# Sampler.net
KiCad netlist of a schematic drawn in Altium Designer
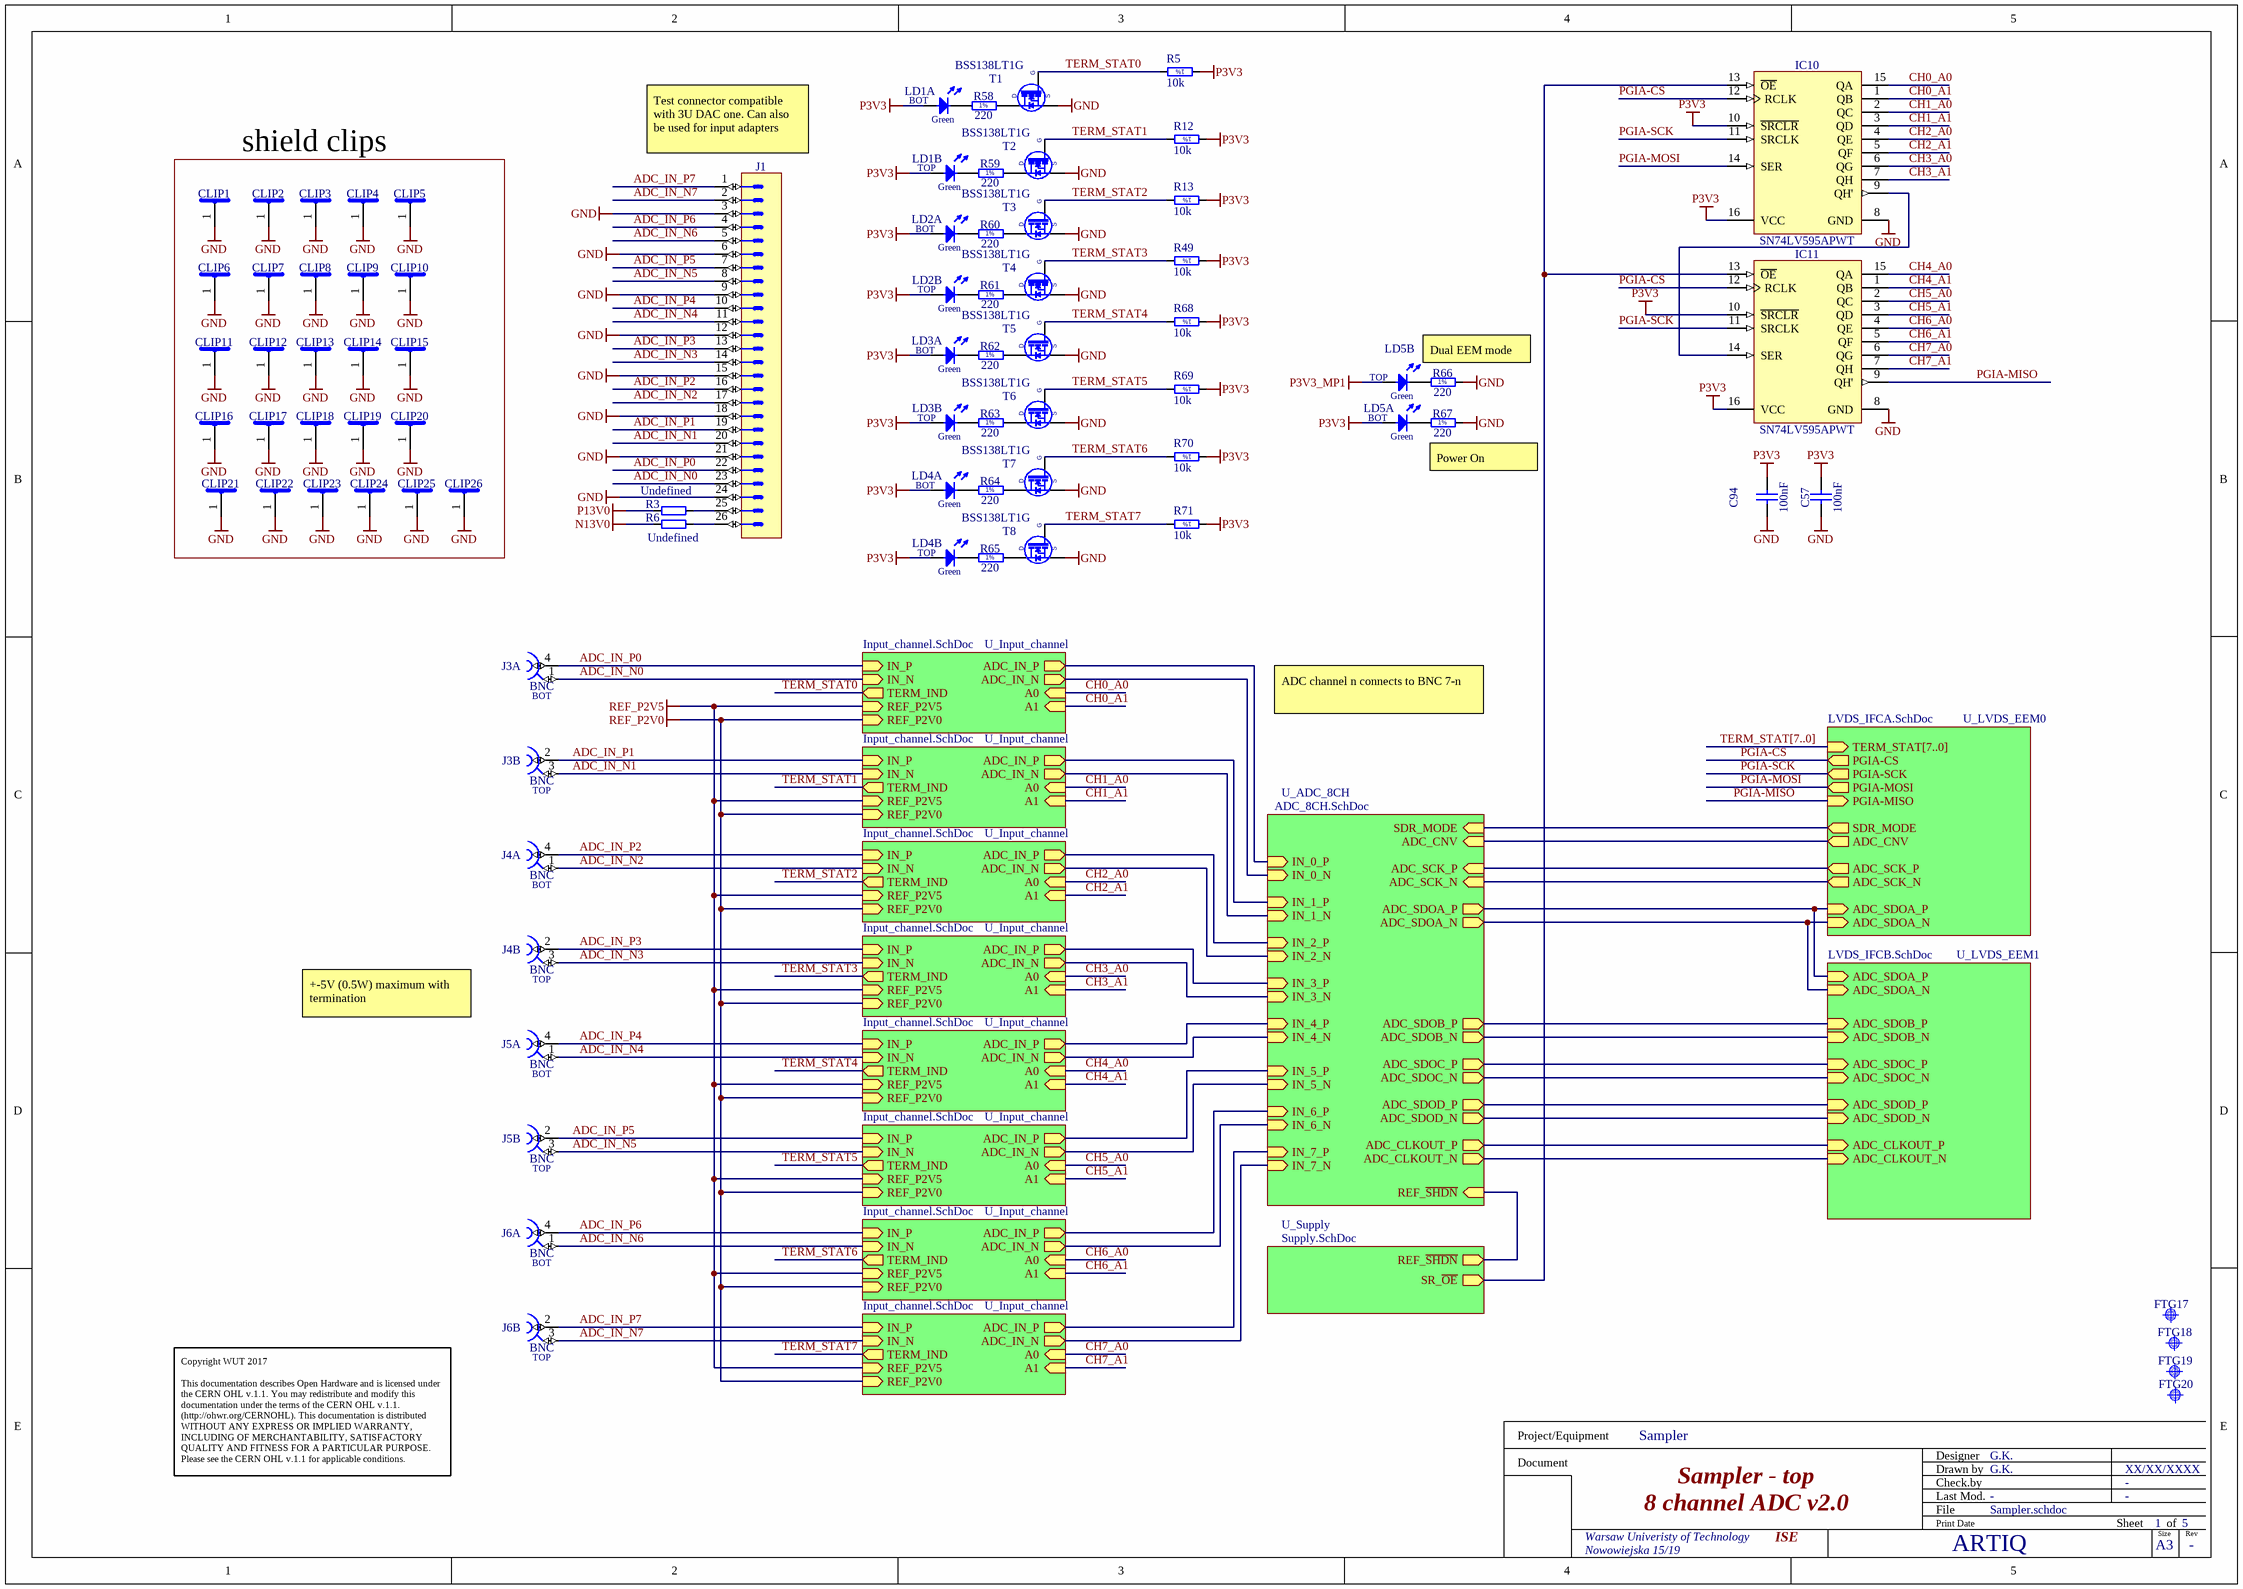
[diagram p0: Sampler.schdoc]

(export (version "E")
  (design (tool "Eeschema 10.0.6"))
  (components
    (comp (ref "C57")
      (value "100nF")
      (footprint "CAPC1608X87N")
      (description "Non-polarised capacitor")
      (fields
        (field (name "PART NUMBER") "CC0603_100NF_50V_10%_X7R")
        (field (name "VOLTAGE") "50V")
        (field (name "AUTHOR") "CERN DEM JLC")
      )
      (libsource (lib "Capacitors") (part "Capacitor - non polarized"))
    )
    (comp (ref "C94")
      (value "100nF")
      (footprint "CAPC1608X87N")
      (description "Non-polarised capacitor")
      (fields
        (field (name "PART NUMBER") "CC0603_100NF_50V_10%_X7R")
        (field (name "VOLTAGE") "50V")
        (field (name "AUTHOR") "CERN DEM JLC")
      )
      (libsource (lib "Capacitors") (part "Capacitor - non polarized"))
    )
    (comp (ref "CLIP1")
      (value "S1411-46R")
      (footprint "CLIP_HOLLAND-SHIELDING_LC")
      (description "Surface Mount Clip for PCB Screening Covers")
      (fields (field (name "MANUFACTURER") "HARWIN") (field (name "AUTHOR") "CERN DEM JLC"))
      (libsource (lib "LIBRARY_SCH") (part "SHIELD_CLIP"))
    )
    (comp (ref "CLIP2")
      (value "S1411-46R")
      (footprint "CLIP_HOLLAND-SHIELDING_LC")
      (description "Surface Mount Clip for PCB Screening Covers")
      (fields (field (name "MANUFACTURER") "HARWIN") (field (name "AUTHOR") "CERN DEM JLC"))
      (libsource (lib "LIBRARY_SCH") (part "SHIELD_CLIP"))
    )
    (comp (ref "CLIP3")
      (value "S1411-46R")
      (footprint "CLIP_HOLLAND-SHIELDING_LC")
      (description "Surface Mount Clip for PCB Screening Covers")
      (fields (field (name "MANUFACTURER") "HARWIN") (field (name "AUTHOR") "CERN DEM JLC"))
      (libsource (lib "LIBRARY_SCH") (part "SHIELD_CLIP"))
    )
    (comp (ref "CLIP4")
      (value "S1411-46R")
      (footprint "CLIP_HOLLAND-SHIELDING_LC")
      (description "Surface Mount Clip for PCB Screening Covers")
      (fields (field (name "MANUFACTURER") "HARWIN") (field (name "AUTHOR") "CERN DEM JLC"))
      (libsource (lib "LIBRARY_SCH") (part "SHIELD_CLIP"))
    )
    (comp (ref "CLIP5")
      (value "S1411-46R")
      (footprint "CLIP_HOLLAND-SHIELDING_LC")
      (description "Surface Mount Clip for PCB Screening Covers")
      (fields (field (name "MANUFACTURER") "HARWIN") (field (name "AUTHOR") "CERN DEM JLC"))
      (libsource (lib "LIBRARY_SCH") (part "SHIELD_CLIP"))
    )
    (comp (ref "CLIP6")
      (value "S1411-46R")
      (footprint "CLIP_HOLLAND-SHIELDING_LC")
      (description "Surface Mount Clip for PCB Screening Covers")
      (fields (field (name "MANUFACTURER") "HARWIN") (field (name "AUTHOR") "CERN DEM JLC"))
      (libsource (lib "LIBRARY_SCH") (part "SHIELD_CLIP"))
    )
    (comp (ref "CLIP7")
      (value "S1411-46R")
      (footprint "CLIP_HOLLAND-SHIELDING_LC")
      (description "Surface Mount Clip for PCB Screening Covers")
      (fields (field (name "MANUFACTURER") "HARWIN") (field (name "AUTHOR") "CERN DEM JLC"))
      (libsource (lib "LIBRARY_SCH") (part "SHIELD_CLIP"))
    )
    (comp (ref "CLIP8")
      (value "S1411-46R")
      (footprint "CLIP_HOLLAND-SHIELDING_LC")
      (description "Surface Mount Clip for PCB Screening Covers")
      (fields (field (name "MANUFACTURER") "HARWIN") (field (name "AUTHOR") "CERN DEM JLC"))
      (libsource (lib "LIBRARY_SCH") (part "SHIELD_CLIP"))
    )
    (comp (ref "CLIP9")
      (value "S1411-46R")
      (footprint "CLIP_HOLLAND-SHIELDING_LC")
      (description "Surface Mount Clip for PCB Screening Covers")
      (fields (field (name "MANUFACTURER") "HARWIN") (field (name "AUTHOR") "CERN DEM JLC"))
      (libsource (lib "LIBRARY_SCH") (part "SHIELD_CLIP"))
    )
    (comp (ref "CLIP10")
      (value "S1411-46R")
      (footprint "CLIP_HOLLAND-SHIELDING_LC")
      (description "Surface Mount Clip for PCB Screening Covers")
      (fields (field (name "MANUFACTURER") "HARWIN") (field (name "AUTHOR") "CERN DEM JLC"))
      (libsource (lib "LIBRARY_SCH") (part "SHIELD_CLIP"))
    )
    (comp (ref "CLIP11")
      (value "S1411-46R")
      (footprint "CLIP_HOLLAND-SHIELDING_LC")
      (description "Surface Mount Clip for PCB Screening Covers")
      (fields (field (name "MANUFACTURER") "HARWIN") (field (name "AUTHOR") "CERN DEM JLC"))
      (libsource (lib "LIBRARY_SCH") (part "SHIELD_CLIP"))
    )
    (comp (ref "CLIP12")
      (value "S1411-46R")
      (footprint "CLIP_HOLLAND-SHIELDING_LC")
      (description "Surface Mount Clip for PCB Screening Covers")
      (fields (field (name "MANUFACTURER") "HARWIN") (field (name "AUTHOR") "CERN DEM JLC"))
      (libsource (lib "LIBRARY_SCH") (part "SHIELD_CLIP"))
    )
    (comp (ref "CLIP13")
      (value "S1411-46R")
      (footprint "CLIP_HOLLAND-SHIELDING_LC")
      (description "Surface Mount Clip for PCB Screening Covers")
      (fields (field (name "MANUFACTURER") "HARWIN") (field (name "AUTHOR") "CERN DEM JLC"))
      (libsource (lib "LIBRARY_SCH") (part "SHIELD_CLIP"))
    )
    (comp (ref "CLIP14")
      (value "S1411-46R")
      (footprint "CLIP_HOLLAND-SHIELDING_LC")
      (description "Surface Mount Clip for PCB Screening Covers")
      (fields (field (name "MANUFACTURER") "HARWIN") (field (name "AUTHOR") "CERN DEM JLC"))
      (libsource (lib "LIBRARY_SCH") (part "SHIELD_CLIP"))
    )
    (comp (ref "CLIP15")
      (value "S1411-46R")
      (footprint "CLIP_HOLLAND-SHIELDING_LC")
      (description "Surface Mount Clip for PCB Screening Covers")
      (fields (field (name "MANUFACTURER") "HARWIN") (field (name "AUTHOR") "CERN DEM JLC"))
      (libsource (lib "LIBRARY_SCH") (part "SHIELD_CLIP"))
    )
    (comp (ref "CLIP16")
      (value "S1411-46R")
      (footprint "CLIP_HOLLAND-SHIELDING_LC")
      (description "Surface Mount Clip for PCB Screening Covers")
      (fields (field (name "MANUFACTURER") "HARWIN") (field (name "AUTHOR") "CERN DEM JLC"))
      (libsource (lib "LIBRARY_SCH") (part "SHIELD_CLIP"))
    )
    (comp (ref "CLIP17")
      (value "S1411-46R")
      (footprint "CLIP_HOLLAND-SHIELDING_LC")
      (description "Surface Mount Clip for PCB Screening Covers")
      (fields (field (name "MANUFACTURER") "HARWIN") (field (name "AUTHOR") "CERN DEM JLC"))
      (libsource (lib "LIBRARY_SCH") (part "SHIELD_CLIP"))
    )
    (comp (ref "CLIP18")
      (value "S1411-46R")
      (footprint "CLIP_HOLLAND-SHIELDING_LC")
      (description "Surface Mount Clip for PCB Screening Covers")
      (fields (field (name "MANUFACTURER") "HARWIN") (field (name "AUTHOR") "CERN DEM JLC"))
      (libsource (lib "LIBRARY_SCH") (part "SHIELD_CLIP"))
    )
    (comp (ref "CLIP19")
      (value "S1411-46R")
      (footprint "CLIP_HOLLAND-SHIELDING_LC")
      (description "Surface Mount Clip for PCB Screening Covers")
      (fields (field (name "MANUFACTURER") "HARWIN") (field (name "AUTHOR") "CERN DEM JLC"))
      (libsource (lib "LIBRARY_SCH") (part "SHIELD_CLIP"))
    )
    (comp (ref "CLIP20")
      (value "S1411-46R")
      (footprint "CLIP_HOLLAND-SHIELDING_LC")
      (description "Surface Mount Clip for PCB Screening Covers")
      (fields (field (name "MANUFACTURER") "HARWIN") (field (name "AUTHOR") "CERN DEM JLC"))
      (libsource (lib "LIBRARY_SCH") (part "SHIELD_CLIP"))
    )
    (comp (ref "CLIP21")
      (value "S1411-46R")
      (footprint "CLIP_HOLLAND-SHIELDING_LC")
      (description "Surface Mount Clip for PCB Screening Covers")
      (fields (field (name "MANUFACTURER") "HARWIN") (field (name "AUTHOR") "CERN DEM JLC"))
      (libsource (lib "LIBRARY_SCH") (part "SHIELD_CLIP"))
    )
    (comp (ref "CLIP22")
      (value "S1411-46R")
      (footprint "CLIP_HOLLAND-SHIELDING_LC")
      (description "Surface Mount Clip for PCB Screening Covers")
      (fields (field (name "MANUFACTURER") "HARWIN") (field (name "AUTHOR") "CERN DEM JLC"))
      (libsource (lib "LIBRARY_SCH") (part "SHIELD_CLIP"))
    )
    (comp (ref "CLIP23")
      (value "S1411-46R")
      (footprint "CLIP_HOLLAND-SHIELDING_LC")
      (description "Surface Mount Clip for PCB Screening Covers")
      (fields (field (name "MANUFACTURER") "HARWIN") (field (name "AUTHOR") "CERN DEM JLC"))
      (libsource (lib "LIBRARY_SCH") (part "SHIELD_CLIP"))
    )
    (comp (ref "CLIP24")
      (value "S1411-46R")
      (footprint "CLIP_HOLLAND-SHIELDING_LC")
      (description "Surface Mount Clip for PCB Screening Covers")
      (fields (field (name "MANUFACTURER") "HARWIN") (field (name "AUTHOR") "CERN DEM JLC"))
      (libsource (lib "LIBRARY_SCH") (part "SHIELD_CLIP"))
    )
    (comp (ref "CLIP25")
      (value "S1411-46R")
      (footprint "CLIP_HOLLAND-SHIELDING_LC")
      (description "Surface Mount Clip for PCB Screening Covers")
      (fields (field (name "MANUFACTURER") "HARWIN") (field (name "AUTHOR") "CERN DEM JLC"))
      (libsource (lib "LIBRARY_SCH") (part "SHIELD_CLIP"))
    )
    (comp (ref "CLIP26")
      (value "S1411-46R")
      (footprint "CLIP_HOLLAND-SHIELDING_LC")
      (description "Surface Mount Clip for PCB Screening Covers")
      (fields (field (name "MANUFACTURER") "HARWIN") (field (name "AUTHOR") "CERN DEM JLC"))
      (libsource (lib "LIBRARY_SCH") (part "SHIELD_CLIP"))
    )
    (comp (ref "FTG17")
      (value "Use only in PCB")
      (footprint "FIDUCIAL_TOP_C100-200")
      (description "Fiducial Target")
      (fields (field (name "PART NUMBER") "FIDUCIAL_TARGET_C100-200") (field (name "AUTHOR") "CERN DEM JLC"))
      (libsource (lib "Eletro-mechanical") (part "Fiducial Target"))
    )
    (comp (ref "FTG18")
      (value "Use only in PCB")
      (footprint "FIDUCIAL_TOP_S100-200")
      (description "Fiducial Target")
      (fields (field (name "PART NUMBER") "FIDUCIAL_TARGET_S100-200") (field (name "AUTHOR") "CERN DEM JLC"))
      (libsource (lib "Eletro-mechanical") (part "Fiducial Target"))
    )
    (comp (ref "FTG19")
      (value "Use only in PCB")
      (footprint "FIDUCIAL_TOP_S200-400")
      (description "Fiducial Target")
      (fields (field (name "PART NUMBER") "FIDUCIAL_TARGET_S200-400") (field (name "AUTHOR") "CERN DEM JLC"))
      (libsource (lib "Eletro-mechanical") (part "Fiducial Target"))
    )
    (comp (ref "FTG20")
      (value "Use only in PCB")
      (footprint "FIDUCIAL_TOP_S100-200")
      (description "Fiducial Target")
      (fields (field (name "PART NUMBER") "FIDUCIAL_TARGET_S100-200") (field (name "AUTHOR") "CERN DEM JLC"))
      (libsource (lib "Eletro-mechanical") (part "Fiducial Target"))
    )
    (comp (ref "IC10")
      (value "SN74LV595APWT")
      (footprint "SOP65P640X120-16N")
      (description "8-Bit Shift Register With 3-State Output Register")
      (fields (field (name "MANUFACTURER") "TEXAS INSTRUMENTS") (field (name "AUTHOR") "CERN DEM JLC"))
      (libsource (lib "ICs And Semiconductors") (part "74595"))
    )
    (comp (ref "IC11")
      (value "SN74LV595APWT")
      (footprint "SOP65P640X120-16N")
      (description "8-Bit Shift Register With 3-State Output Register")
      (fields (field (name "MANUFACTURER") "TEXAS INSTRUMENTS") (field (name "AUTHOR") "CERN DEM JLC"))
      (libsource (lib "ICs And Semiconductors") (part "74595"))
    )
    (comp (ref "J1")
      (value "Header 26")
      (footprint "3M_N2526-6002RB")
      (description "Connector 26 Male")
      (fields
        (field (name "PART NUMBER") "3M_N2526-6002RB")
        (field (name "MANUFACTURER") "3M")
        (field (name "AUTHOR") "CERN DEM JLC")
      )
      (libsource (lib "Connectors") (part "Connector 26 Male"))
    )
    (comp (ref "J3")
      (value "BNC")
      (footprint "RENHOTEC_RHT-610-0049")
      (description "Dual Right Angle 50 Ohm BNC Jack, White Valox Case")
      (fields
        (field (name "PART NUMBER") "RENHOTEC_RHT-610-0049")
        (field (name "MANUFACTURER") "RENHOTEC")
        (field (name "AUTHOR") "GK")
      )
      (libsource (lib "LIBRARY_SCH") (part "CON_BNC_DUAL"))
    )
    (comp (ref "J4")
      (value "BNC")
      (footprint "RENHOTEC_RHT-610-0049")
      (description "Dual Right Angle 50 Ohm BNC Jack, White Valox Case")
      (fields
        (field (name "PART NUMBER") "RENHOTEC_RHT-610-0049")
        (field (name "MANUFACTURER") "RENHOTEC")
        (field (name "AUTHOR") "GK")
      )
      (libsource (lib "LIBRARY_SCH") (part "CON_BNC_DUAL"))
    )
    (comp (ref "J5")
      (value "BNC")
      (footprint "RENHOTEC_RHT-610-0049")
      (description "Dual Right Angle 50 Ohm BNC Jack, White Valox Case")
      (fields
        (field (name "PART NUMBER") "RENHOTEC_RHT-610-0049")
        (field (name "MANUFACTURER") "RENHOTEC")
        (field (name "AUTHOR") "GK")
      )
      (libsource (lib "LIBRARY_SCH") (part "CON_BNC_DUAL"))
    )
    (comp (ref "J6")
      (value "BNC")
      (footprint "RENHOTEC_RHT-610-0049")
      (description "Dual Right Angle 50 Ohm BNC Jack, White Valox Case")
      (fields
        (field (name "PART NUMBER") "RENHOTEC_RHT-610-0049")
        (field (name "MANUFACTURER") "RENHOTEC")
        (field (name "AUTHOR") "GK")
      )
      (libsource (lib "LIBRARY_SCH") (part "CON_BNC_DUAL"))
    )
    (comp (ref "LD1")
      (value "Green/Green")
      (footprint "LED_DIALIGHT_571-0122F")
      (description "LED x2 Green 1C2A-BOT_3C4A-TOP")
      (fields
        (field (name "PART NUMBER") "LED_DIALIGHT_571-0122F")
        (field (name "MANUFACTURER") "DIALIGHT")
        (field (name "AUTHOR") "CERN DEM JLC")
      )
      (libsource (lib "ICs And Semiconductors") (part "LED x2 Green 1C2A-BOT_3C4A-TOP"))
    )
    (comp (ref "LD2")
      (value "Green/Green")
      (footprint "LED_DIALIGHT_571-0122F")
      (description "LED x2 Green 1C2A-BOT_3C4A-TOP")
      (fields
        (field (name "PART NUMBER") "LED_DIALIGHT_571-0122F")
        (field (name "MANUFACTURER") "DIALIGHT")
        (field (name "AUTHOR") "CERN DEM JLC")
      )
      (libsource (lib "ICs And Semiconductors") (part "LED x2 Green 1C2A-BOT_3C4A-TOP"))
    )
    (comp (ref "LD3")
      (value "Green/Green")
      (footprint "LED_DIALIGHT_571-0122F")
      (description "LED x2 Green 1C2A-BOT_3C4A-TOP")
      (fields
        (field (name "PART NUMBER") "LED_DIALIGHT_571-0122F")
        (field (name "MANUFACTURER") "DIALIGHT")
        (field (name "AUTHOR") "CERN DEM JLC")
      )
      (libsource (lib "ICs And Semiconductors") (part "LED x2 Green 1C2A-BOT_3C4A-TOP"))
    )
    (comp (ref "LD4")
      (value "Green/Green")
      (footprint "LED_DIALIGHT_571-0122F")
      (description "LED x2 Green 1C2A-BOT_3C4A-TOP")
      (fields
        (field (name "PART NUMBER") "LED_DIALIGHT_571-0122F")
        (field (name "MANUFACTURER") "DIALIGHT")
        (field (name "AUTHOR") "CERN DEM JLC")
      )
      (libsource (lib "ICs And Semiconductors") (part "LED x2 Green 1C2A-BOT_3C4A-TOP"))
    )
    (comp (ref "LD5")
      (value "Green/Green")
      (footprint "LED_DIALIGHT_571-0122F")
      (description "LED x2 Green 1C2A-BOT_3C4A-TOP")
      (fields
        (field (name "PART NUMBER") "LED_DIALIGHT_571-0122F")
        (field (name "MANUFACTURER") "DIALIGHT")
        (field (name "AUTHOR") "CERN DEM JLC")
      )
      (libsource (lib "ICs And Semiconductors") (part "LED x2 Green 1C2A-BOT_3C4A-TOP"))
    )
    (comp (ref "R3")
      (value "Undefined")
      (footprint "RESC1608X55N")
      (description "Resistor")
      (fields (field (name "PART NUMBER") "R0603_NO-VALUE") (field (name "AUTHOR") "CERN DEM JLC"))
      (libsource (lib "Resistors") (part "Resistor"))
    )
    (comp (ref "R5")
      (value "10k")
      (footprint "RESC1005X40N")
      (description "Resistor - 1%")
      (fields
        (field (name "PART NUMBER") "R0402_10K_1%_0.0625W_100PPM")
        (field (name "POWER") "0.0625W")
        (field (name "AUTHOR") "CERN DEM JLC")
      )
      (libsource (lib "Resistors") (part "Resistor - 1%"))
    )
    (comp (ref "R6")
      (value "Undefined")
      (footprint "RESC1608X55N")
      (description "Resistor")
      (fields (field (name "PART NUMBER") "R0603_NO-VALUE") (field (name "AUTHOR") "CERN DEM JLC"))
      (libsource (lib "Resistors") (part "Resistor"))
    )
    (comp (ref "R12")
      (value "10k")
      (footprint "RESC1005X40N")
      (description "Resistor - 1%")
      (fields
        (field (name "PART NUMBER") "R0402_10K_1%_0.0625W_100PPM")
        (field (name "POWER") "0.0625W")
        (field (name "AUTHOR") "CERN DEM JLC")
      )
      (libsource (lib "Resistors") (part "Resistor - 1%"))
    )
    (comp (ref "R13")
      (value "10k")
      (footprint "RESC1005X40N")
      (description "Resistor - 1%")
      (fields
        (field (name "PART NUMBER") "R0402_10K_1%_0.0625W_100PPM")
        (field (name "POWER") "0.0625W")
        (field (name "AUTHOR") "CERN DEM JLC")
      )
      (libsource (lib "Resistors") (part "Resistor - 1%"))
    )
    (comp (ref "R49")
      (value "10k")
      (footprint "RESC1005X40N")
      (description "Resistor - 1%")
      (fields
        (field (name "PART NUMBER") "R0402_10K_1%_0.0625W_100PPM")
        (field (name "POWER") "0.0625W")
        (field (name "AUTHOR") "CERN DEM JLC")
      )
      (libsource (lib "Resistors") (part "Resistor - 1%"))
    )
    (comp (ref "R58")
      (value "220")
      (footprint "RESC1608X55N")
      (description "Resistor - 1%")
      (fields
        (field (name "PART NUMBER") "R0603_220R_1%_0.1W_100PPM")
        (field (name "POWER") "0.1W")
        (field (name "AUTHOR") "CERN DEM JLC")
      )
      (libsource (lib "Resistors") (part "Resistor - 1%"))
    )
    (comp (ref "R59")
      (value "220")
      (footprint "RESC1608X55N")
      (description "Resistor - 1%")
      (fields
        (field (name "PART NUMBER") "R0603_220R_1%_0.1W_100PPM")
        (field (name "POWER") "0.1W")
        (field (name "AUTHOR") "CERN DEM JLC")
      )
      (libsource (lib "Resistors") (part "Resistor - 1%"))
    )
    (comp (ref "R60")
      (value "220")
      (footprint "RESC1608X55N")
      (description "Resistor - 1%")
      (fields
        (field (name "PART NUMBER") "R0603_220R_1%_0.1W_100PPM")
        (field (name "POWER") "0.1W")
        (field (name "AUTHOR") "CERN DEM JLC")
      )
      (libsource (lib "Resistors") (part "Resistor - 1%"))
    )
    (comp (ref "R61")
      (value "220")
      (footprint "RESC1608X55N")
      (description "Resistor - 1%")
      (fields
        (field (name "PART NUMBER") "R0603_220R_1%_0.1W_100PPM")
        (field (name "POWER") "0.1W")
        (field (name "AUTHOR") "CERN DEM JLC")
      )
      (libsource (lib "Resistors") (part "Resistor - 1%"))
    )
    (comp (ref "R62")
      (value "220")
      (footprint "RESC1608X55N")
      (description "Resistor - 1%")
      (fields
        (field (name "PART NUMBER") "R0603_220R_1%_0.1W_100PPM")
        (field (name "POWER") "0.1W")
        (field (name "AUTHOR") "CERN DEM JLC")
      )
      (libsource (lib "Resistors") (part "Resistor - 1%"))
    )
    (comp (ref "R63")
      (value "220")
      (footprint "RESC1608X55N")
      (description "Resistor - 1%")
      (fields
        (field (name "PART NUMBER") "R0603_220R_1%_0.1W_100PPM")
        (field (name "POWER") "0.1W")
        (field (name "AUTHOR") "CERN DEM JLC")
      )
      (libsource (lib "Resistors") (part "Resistor - 1%"))
    )
    (comp (ref "R64")
      (value "220")
      (footprint "RESC1608X55N")
      (description "Resistor - 1%")
      (fields
        (field (name "PART NUMBER") "R0603_220R_1%_0.1W_100PPM")
        (field (name "POWER") "0.1W")
        (field (name "AUTHOR") "CERN DEM JLC")
      )
      (libsource (lib "Resistors") (part "Resistor - 1%"))
    )
    (comp (ref "R65")
      (value "220")
      (footprint "RESC1608X55N")
      (description "Resistor - 1%")
      (fields
        (field (name "PART NUMBER") "R0603_220R_1%_0.1W_100PPM")
        (field (name "POWER") "0.1W")
        (field (name "AUTHOR") "CERN DEM JLC")
      )
      (libsource (lib "Resistors") (part "Resistor - 1%"))
    )
    (comp (ref "R66")
      (value "220")
      (footprint "RESC1608X55N")
      (description "Resistor - 1%")
      (fields
        (field (name "PART NUMBER") "R0603_220R_1%_0.1W_100PPM")
        (field (name "POWER") "0.1W")
        (field (name "AUTHOR") "CERN DEM JLC")
      )
      (libsource (lib "Resistors") (part "Resistor - 1%"))
    )
    (comp (ref "R67")
      (value "220")
      (footprint "RESC1608X55N")
      (description "Resistor - 1%")
      (fields
        (field (name "PART NUMBER") "R0603_220R_1%_0.1W_100PPM")
        (field (name "POWER") "0.1W")
        (field (name "AUTHOR") "CERN DEM JLC")
      )
      (libsource (lib "Resistors") (part "Resistor - 1%"))
    )
    (comp (ref "R68")
      (value "10k")
      (footprint "RESC1005X40N")
      (description "Resistor - 1%")
      (fields
        (field (name "PART NUMBER") "R0402_10K_1%_0.0625W_100PPM")
        (field (name "POWER") "0.0625W")
        (field (name "AUTHOR") "CERN DEM JLC")
      )
      (libsource (lib "Resistors") (part "Resistor - 1%"))
    )
    (comp (ref "R69")
      (value "10k")
      (footprint "RESC1005X40N")
      (description "Resistor - 1%")
      (fields
        (field (name "PART NUMBER") "R0402_10K_1%_0.0625W_100PPM")
        (field (name "POWER") "0.0625W")
        (field (name "AUTHOR") "CERN DEM JLC")
      )
      (libsource (lib "Resistors") (part "Resistor - 1%"))
    )
    (comp (ref "R70")
      (value "10k")
      (footprint "RESC1005X40N")
      (description "Resistor - 1%")
      (fields
        (field (name "PART NUMBER") "R0402_10K_1%_0.0625W_100PPM")
        (field (name "POWER") "0.0625W")
        (field (name "AUTHOR") "CERN DEM JLC")
      )
      (libsource (lib "Resistors") (part "Resistor - 1%"))
    )
    (comp (ref "R71")
      (value "10k")
      (footprint "RESC1005X40N")
      (description "Resistor - 1%")
      (fields
        (field (name "PART NUMBER") "R0402_10K_1%_0.0625W_100PPM")
        (field (name "POWER") "0.0625W")
        (field (name "AUTHOR") "CERN DEM JLC")
      )
      (libsource (lib "Resistors") (part "Resistor - 1%"))
    )
    (comp (ref "T1")
      (value "BSS138LT1G")
      (footprint "SOT95P240X110-3N")
      (description "N-CHANNEL MOSFET WITH DIODE")
      (fields (field (name "MANUFACTURER") "ON SEMICONDUCTOR") (field (name "AUTHOR") "CERN DEM JLC"))
      (libsource (lib "ICs And Semiconductors") (part "N-MOSFET-D 1G 2S 3D"))
    )
    (comp (ref "T2")
      (value "BSS138LT1G")
      (footprint "SOT95P240X110-3N")
      (description "N-CHANNEL MOSFET WITH DIODE")
      (fields (field (name "MANUFACTURER") "ON SEMICONDUCTOR") (field (name "AUTHOR") "CERN DEM JLC"))
      (libsource (lib "ICs And Semiconductors") (part "N-MOSFET-D 1G 2S 3D"))
    )
    (comp (ref "T3")
      (value "BSS138LT1G")
      (footprint "SOT95P240X110-3N")
      (description "N-CHANNEL MOSFET WITH DIODE")
      (fields (field (name "MANUFACTURER") "ON SEMICONDUCTOR") (field (name "AUTHOR") "CERN DEM JLC"))
      (libsource (lib "ICs And Semiconductors") (part "N-MOSFET-D 1G 2S 3D"))
    )
    (comp (ref "T4")
      (value "BSS138LT1G")
      (footprint "SOT95P240X110-3N")
      (description "N-CHANNEL MOSFET WITH DIODE")
      (fields (field (name "MANUFACTURER") "ON SEMICONDUCTOR") (field (name "AUTHOR") "CERN DEM JLC"))
      (libsource (lib "ICs And Semiconductors") (part "N-MOSFET-D 1G 2S 3D"))
    )
    (comp (ref "T5")
      (value "BSS138LT1G")
      (footprint "SOT95P240X110-3N")
      (description "N-CHANNEL MOSFET WITH DIODE")
      (fields (field (name "MANUFACTURER") "ON SEMICONDUCTOR") (field (name "AUTHOR") "CERN DEM JLC"))
      (libsource (lib "ICs And Semiconductors") (part "N-MOSFET-D 1G 2S 3D"))
    )
    (comp (ref "T6")
      (value "BSS138LT1G")
      (footprint "SOT95P240X110-3N")
      (description "N-CHANNEL MOSFET WITH DIODE")
      (fields (field (name "MANUFACTURER") "ON SEMICONDUCTOR") (field (name "AUTHOR") "CERN DEM JLC"))
      (libsource (lib "ICs And Semiconductors") (part "N-MOSFET-D 1G 2S 3D"))
    )
    (comp (ref "T7")
      (value "BSS138LT1G")
      (footprint "SOT95P240X110-3N")
      (description "N-CHANNEL MOSFET WITH DIODE")
      (fields (field (name "MANUFACTURER") "ON SEMICONDUCTOR") (field (name "AUTHOR") "CERN DEM JLC"))
      (libsource (lib "ICs And Semiconductors") (part "N-MOSFET-D 1G 2S 3D"))
    )
    (comp (ref "T8")
      (value "BSS138LT1G")
      (footprint "SOT95P240X110-3N")
      (description "N-CHANNEL MOSFET WITH DIODE")
      (fields (field (name "MANUFACTURER") "ON SEMICONDUCTOR") (field (name "AUTHOR") "CERN DEM JLC"))
      (libsource (lib "ICs And Semiconductors") (part "N-MOSFET-D 1G 2S 3D"))
    )
  )
  (nets
    (net (code "5") (name "/ADC_IN_N0") (class "Default")
      (node (ref "J1") (pin "23") (pinfunction "23_23") (pintype "bidirectional"))
      (node (ref "J3") (pin "1") (pinfunction "1_1") (pintype "bidirectional"))
    )
    (net (code "6") (name "/ADC_IN_N1") (class "Default")
      (node (ref "J1") (pin "20") (pinfunction "20_20") (pintype "bidirectional"))
      (node (ref "J3") (pin "3") (pinfunction "3_3") (pintype "bidirectional"))
    )
    (net (code "7") (name "/ADC_IN_N2") (class "Default")
      (node (ref "J1") (pin "17") (pinfunction "17_17") (pintype "bidirectional"))
      (node (ref "J4") (pin "1") (pinfunction "1_1") (pintype "bidirectional"))
    )
    (net (code "8") (name "/ADC_IN_N3") (class "Default")
      (node (ref "J1") (pin "14") (pinfunction "14_14") (pintype "bidirectional"))
      (node (ref "J4") (pin "3") (pinfunction "3_3") (pintype "bidirectional"))
    )
    (net (code "9") (name "/ADC_IN_N4") (class "Default")
      (node (ref "J1") (pin "11") (pinfunction "11_11") (pintype "bidirectional"))
      (node (ref "J5") (pin "1") (pinfunction "1_1") (pintype "bidirectional"))
    )
    (net (code "10") (name "/ADC_IN_N5") (class "Default")
      (node (ref "J1") (pin "8") (pinfunction "8_8") (pintype "bidirectional"))
      (node (ref "J5") (pin "3") (pinfunction "3_3") (pintype "bidirectional"))
    )
    (net (code "11") (name "/ADC_IN_N6") (class "Default")
      (node (ref "J1") (pin "5") (pinfunction "5_5") (pintype "bidirectional"))
      (node (ref "J6") (pin "1") (pinfunction "1_1") (pintype "bidirectional"))
    )
    (net (code "12") (name "/ADC_IN_N7") (class "Default")
      (node (ref "J1") (pin "2") (pinfunction "2_2") (pintype "bidirectional"))
      (node (ref "J6") (pin "3") (pinfunction "3_3") (pintype "bidirectional"))
    )
    (net (code "21") (name "/ADC_IN_P0") (class "Default")
      (node (ref "J1") (pin "22") (pinfunction "22_22") (pintype "bidirectional"))
      (node (ref "J3") (pin "4") (pinfunction "4_4") (pintype "bidirectional"))
    )
    (net (code "22") (name "/ADC_IN_P1") (class "Default")
      (node (ref "J1") (pin "19") (pinfunction "19_19") (pintype "bidirectional"))
      (node (ref "J3") (pin "2") (pinfunction "2_2") (pintype "bidirectional"))
    )
    (net (code "23") (name "/ADC_IN_P2") (class "Default")
      (node (ref "J1") (pin "16") (pinfunction "16_16") (pintype "bidirectional"))
      (node (ref "J4") (pin "4") (pinfunction "4_4") (pintype "bidirectional"))
    )
    (net (code "24") (name "/ADC_IN_P3") (class "Default")
      (node (ref "J1") (pin "13") (pinfunction "13_13") (pintype "bidirectional"))
      (node (ref "J4") (pin "2") (pinfunction "2_2") (pintype "bidirectional"))
    )
    (net (code "25") (name "/ADC_IN_P4") (class "Default")
      (node (ref "J1") (pin "10") (pinfunction "10_10") (pintype "bidirectional"))
      (node (ref "J5") (pin "4") (pinfunction "4_4") (pintype "bidirectional"))
    )
    (net (code "26") (name "/ADC_IN_P5") (class "Default")
      (node (ref "J1") (pin "7") (pinfunction "7_7") (pintype "bidirectional"))
      (node (ref "J5") (pin "2") (pinfunction "2_2") (pintype "bidirectional"))
    )
    (net (code "27") (name "/ADC_IN_P6") (class "Default")
      (node (ref "J1") (pin "4") (pinfunction "4_4") (pintype "bidirectional"))
      (node (ref "J6") (pin "4") (pinfunction "4_4") (pintype "bidirectional"))
    )
    (net (code "28") (name "/ADC_IN_P7") (class "Default")
      (node (ref "J1") (pin "1") (pinfunction "1_1") (pintype "bidirectional"))
      (node (ref "J6") (pin "2") (pinfunction "2_2") (pintype "bidirectional"))
    )
    (net (code "46") (name "/CH0_A0") (class "Default")
      (node (ref "IC10") (pin "15") (pinfunction "QA_15") (pintype "tri_state"))
    )
    (net (code "47") (name "/CH0_A1") (class "Default")
      (node (ref "IC10") (pin "1") (pinfunction "QB_1") (pintype "tri_state"))
    )
    (net (code "48") (name "/CH1_A0") (class "Default")
      (node (ref "IC10") (pin "2") (pinfunction "QC_2") (pintype "tri_state"))
    )
    (net (code "49") (name "/CH1_A1") (class "Default")
      (node (ref "IC10") (pin "3") (pinfunction "QD_3") (pintype "tri_state"))
    )
    (net (code "50") (name "/CH2_A0") (class "Default")
      (node (ref "IC10") (pin "4") (pinfunction "QE_4") (pintype "tri_state"))
    )
    (net (code "51") (name "/CH2_A1") (class "Default")
      (node (ref "IC10") (pin "5") (pinfunction "QF_5") (pintype "tri_state"))
    )
    (net (code "52") (name "/CH3_A0") (class "Default")
      (node (ref "IC10") (pin "6") (pinfunction "QG_6") (pintype "tri_state"))
    )
    (net (code "53") (name "/CH3_A1") (class "Default")
      (node (ref "IC10") (pin "7") (pinfunction "QH_7") (pintype "tri_state"))
    )
    (net (code "54") (name "/CH4_A0") (class "Default")
      (node (ref "IC11") (pin "15") (pinfunction "QA_15") (pintype "tri_state"))
    )
    (net (code "55") (name "/CH4_A1") (class "Default")
      (node (ref "IC11") (pin "1") (pinfunction "QB_1") (pintype "tri_state"))
    )
    (net (code "56") (name "/CH5_A0") (class "Default")
      (node (ref "IC11") (pin "2") (pinfunction "QC_2") (pintype "tri_state"))
    )
    (net (code "57") (name "/CH5_A1") (class "Default")
      (node (ref "IC11") (pin "3") (pinfunction "QD_3") (pintype "tri_state"))
    )
    (net (code "58") (name "/CH6_A0") (class "Default")
      (node (ref "IC11") (pin "4") (pinfunction "QE_4") (pintype "tri_state"))
    )
    (net (code "59") (name "/CH6_A1") (class "Default")
      (node (ref "IC11") (pin "5") (pinfunction "QF_5") (pintype "tri_state"))
    )
    (net (code "60") (name "/CH7_A0") (class "Default")
      (node (ref "IC11") (pin "6") (pinfunction "QG_6") (pintype "tri_state"))
    )
    (net (code "61") (name "/CH7_A1") (class "Default")
      (node (ref "IC11") (pin "7") (pinfunction "QH_7") (pintype "tri_state"))
    )
    (net (code "62") (name "/PGIA-CS") (class "Default")
      (node (ref "IC10") (pin "12") (pinfunction "RCLK_12") (pintype "input"))
      (node (ref "IC11") (pin "12") (pinfunction "RCLK_12") (pintype "input"))
    )
    (net (code "63") (name "/PGIA-MISO") (class "Default")
      (node (ref "IC11") (pin "9") (pinfunction "QH'_9") (pintype "output"))
    )
    (net (code "64") (name "/PGIA-MOSI") (class "Default")
      (node (ref "IC10") (pin "14") (pinfunction "SER_14") (pintype "input"))
    )
    (net (code "65") (name "/PGIA-SCK") (class "Default")
      (node (ref "IC10") (pin "11") (pinfunction "SRCLK_11") (pintype "input"))
      (node (ref "IC11") (pin "11") (pinfunction "SRCLK_11") (pintype "input"))
    )
    (net (code "68") (name "/SR_~{OE}") (class "Default")
      (node (ref "IC10") (pin "13") (pinfunction "~{OE}_13") (pintype "input"))
      (node (ref "IC11") (pin "13") (pinfunction "~{OE}_13") (pintype "input"))
    )
    (net (code "69") (name "/TERM_STAT0") (class "Default")
      (node (ref "R5") (pin "2") (pinfunction "2_2") (pintype "passive"))
      (node (ref "T1") (pin "1") (pinfunction "G_1") (pintype "passive"))
    )
    (net (code "70") (name "/TERM_STAT1") (class "Default")
      (node (ref "R12") (pin "2") (pinfunction "2_2") (pintype "passive"))
      (node (ref "T2") (pin "1") (pinfunction "G_1") (pintype "passive"))
    )
    (net (code "71") (name "/TERM_STAT2") (class "Default")
      (node (ref "R13") (pin "2") (pinfunction "2_2") (pintype "passive"))
      (node (ref "T3") (pin "1") (pinfunction "G_1") (pintype "passive"))
    )
    (net (code "72") (name "/TERM_STAT3") (class "Default")
      (node (ref "R49") (pin "2") (pinfunction "2_2") (pintype "passive"))
      (node (ref "T4") (pin "1") (pinfunction "G_1") (pintype "passive"))
    )
    (net (code "73") (name "/TERM_STAT4") (class "Default")
      (node (ref "R68") (pin "2") (pinfunction "2_2") (pintype "passive"))
      (node (ref "T5") (pin "1") (pinfunction "G_1") (pintype "passive"))
    )
    (net (code "74") (name "/TERM_STAT5") (class "Default")
      (node (ref "R69") (pin "2") (pinfunction "2_2") (pintype "passive"))
      (node (ref "T6") (pin "1") (pinfunction "G_1") (pintype "passive"))
    )
    (net (code "75") (name "/TERM_STAT6") (class "Default")
      (node (ref "R70") (pin "2") (pinfunction "2_2") (pintype "passive"))
      (node (ref "T7") (pin "1") (pinfunction "G_1") (pintype "passive"))
    )
    (net (code "76") (name "/TERM_STAT7") (class "Default")
      (node (ref "R71") (pin "2") (pinfunction "2_2") (pintype "passive"))
      (node (ref "T8") (pin "1") (pinfunction "G_1") (pintype "passive"))
    )
    (net (code "78") (name "GND") (class "Default")
      (node (ref "C57") (pin "1") (pinfunction "1_1") (pintype "passive"))
      (node (ref "C94") (pin "1") (pinfunction "1_1") (pintype "passive"))
      (node (ref "CLIP1") (pin "1") (pinfunction "1_1") (pintype "passive"))
      (node (ref "CLIP10") (pin "1") (pinfunction "1_1") (pintype "passive"))
      (node (ref "CLIP11") (pin "1") (pinfunction "1_1") (pintype "passive"))
      (node (ref "CLIP12") (pin "1") (pinfunction "1_1") (pintype "passive"))
      (node (ref "CLIP13") (pin "1") (pinfunction "1_1") (pintype "passive"))
      (node (ref "CLIP14") (pin "1") (pinfunction "1_1") (pintype "passive"))
      (node (ref "CLIP15") (pin "1") (pinfunction "1_1") (pintype "passive"))
      (node (ref "CLIP16") (pin "1") (pinfunction "1_1") (pintype "passive"))
      (node (ref "CLIP17") (pin "1") (pinfunction "1_1") (pintype "passive"))
      (node (ref "CLIP18") (pin "1") (pinfunction "1_1") (pintype "passive"))
      (node (ref "CLIP19") (pin "1") (pinfunction "1_1") (pintype "passive"))
      (node (ref "CLIP2") (pin "1") (pinfunction "1_1") (pintype "passive"))
      (node (ref "CLIP20") (pin "1") (pinfunction "1_1") (pintype "passive"))
      (node (ref "CLIP21") (pin "1") (pinfunction "1_1") (pintype "passive"))
      (node (ref "CLIP22") (pin "1") (pinfunction "1_1") (pintype "passive"))
      (node (ref "CLIP23") (pin "1") (pinfunction "1_1") (pintype "passive"))
      (node (ref "CLIP24") (pin "1") (pinfunction "1_1") (pintype "passive"))
      (node (ref "CLIP25") (pin "1") (pinfunction "1_1") (pintype "passive"))
      (node (ref "CLIP26") (pin "1") (pinfunction "1_1") (pintype "passive"))
      (node (ref "CLIP3") (pin "1") (pinfunction "1_1") (pintype "passive"))
      (node (ref "CLIP4") (pin "1") (pinfunction "1_1") (pintype "passive"))
      (node (ref "CLIP5") (pin "1") (pinfunction "1_1") (pintype "passive"))
      (node (ref "CLIP6") (pin "1") (pinfunction "1_1") (pintype "passive"))
      (node (ref "CLIP7") (pin "1") (pinfunction "1_1") (pintype "passive"))
      (node (ref "CLIP8") (pin "1") (pinfunction "1_1") (pintype "passive"))
      (node (ref "CLIP9") (pin "1") (pinfunction "1_1") (pintype "passive"))
      (node (ref "IC10") (pin "8") (pinfunction "GND_8") (pintype "power_in"))
      (node (ref "IC11") (pin "8") (pinfunction "GND_8") (pintype "power_in"))
      (node (ref "J1") (pin "12") (pinfunction "12_12") (pintype "bidirectional"))
      (node (ref "J1") (pin "15") (pinfunction "15_15") (pintype "bidirectional"))
      (node (ref "J1") (pin "18") (pinfunction "18_18") (pintype "bidirectional"))
      (node (ref "J1") (pin "21") (pinfunction "21_21") (pintype "bidirectional"))
      (node (ref "J1") (pin "24") (pinfunction "24_24") (pintype "bidirectional"))
      (node (ref "J1") (pin "3") (pinfunction "3_3") (pintype "bidirectional"))
      (node (ref "J1") (pin "6") (pinfunction "6_6") (pintype "bidirectional"))
      (node (ref "J1") (pin "9") (pinfunction "9_9") (pintype "bidirectional"))
      (node (ref "R66") (pin "2") (pinfunction "2_2") (pintype "passive"))
      (node (ref "R67") (pin "2") (pinfunction "2_2") (pintype "passive"))
      (node (ref "T1") (pin "2") (pinfunction "S_2") (pintype "passive"))
      (node (ref "T2") (pin "2") (pinfunction "S_2") (pintype "passive"))
      (node (ref "T3") (pin "2") (pinfunction "S_2") (pintype "passive"))
      (node (ref "T4") (pin "2") (pinfunction "S_2") (pintype "passive"))
      (node (ref "T5") (pin "2") (pinfunction "S_2") (pintype "passive"))
      (node (ref "T6") (pin "2") (pinfunction "S_2") (pintype "passive"))
      (node (ref "T7") (pin "2") (pinfunction "S_2") (pintype "passive"))
      (node (ref "T8") (pin "2") (pinfunction "S_2") (pintype "passive"))
    )
    (net (code "79") (name "N13V0") (class "Default")
      (node (ref "R6") (pin "2") (pinfunction "2_2") (pintype "passive"))
    )
    (net (code "80") (name "Net-(IC10-QH')") (class "Default")
      (node (ref "IC10") (pin "9") (pinfunction "QH'_9") (pintype "output"))
      (node (ref "IC11") (pin "14") (pinfunction "SER_14") (pintype "input"))
    )
    (net (code "81") (name "Net-(J1-Pad25)") (class "Default")
      (node (ref "J1") (pin "25") (pinfunction "25_25") (pintype "bidirectional"))
      (node (ref "R3") (pin "1") (pinfunction "1_1") (pintype "passive"))
    )
    (net (code "82") (name "Net-(J1-Pad26)") (class "Default")
      (node (ref "J1") (pin "26") (pinfunction "26_26") (pintype "bidirectional"))
      (node (ref "R6") (pin "1") (pinfunction "1_1") (pintype "passive"))
    )
    (net (code "83") (name "Net-(LD1A-C)") (class "Default")
      (node (ref "LD1") (pin "1") (pinfunction "C_1") (pintype "passive"))
      (node (ref "R58") (pin "1") (pinfunction "1_1") (pintype "passive"))
    )
    (net (code "84") (name "Net-(LD1B-C)") (class "Default")
      (node (ref "LD1") (pin "3") (pinfunction "C_3") (pintype "passive"))
      (node (ref "R59") (pin "1") (pinfunction "1_1") (pintype "passive"))
    )
    (net (code "85") (name "Net-(LD2A-C)") (class "Default")
      (node (ref "LD2") (pin "1") (pinfunction "C_1") (pintype "passive"))
      (node (ref "R60") (pin "1") (pinfunction "1_1") (pintype "passive"))
    )
    (net (code "86") (name "Net-(LD2B-C)") (class "Default")
      (node (ref "LD2") (pin "3") (pinfunction "C_3") (pintype "passive"))
      (node (ref "R61") (pin "1") (pinfunction "1_1") (pintype "passive"))
    )
    (net (code "87") (name "Net-(LD3A-C)") (class "Default")
      (node (ref "LD3") (pin "1") (pinfunction "C_1") (pintype "passive"))
      (node (ref "R62") (pin "1") (pinfunction "1_1") (pintype "passive"))
    )
    (net (code "88") (name "Net-(LD3B-C)") (class "Default")
      (node (ref "LD3") (pin "3") (pinfunction "C_3") (pintype "passive"))
      (node (ref "R63") (pin "1") (pinfunction "1_1") (pintype "passive"))
    )
    (net (code "89") (name "Net-(LD4A-C)") (class "Default")
      (node (ref "LD4") (pin "1") (pinfunction "C_1") (pintype "passive"))
      (node (ref "R64") (pin "1") (pinfunction "1_1") (pintype "passive"))
    )
    (net (code "90") (name "Net-(LD4B-C)") (class "Default")
      (node (ref "LD4") (pin "3") (pinfunction "C_3") (pintype "passive"))
      (node (ref "R65") (pin "1") (pinfunction "1_1") (pintype "passive"))
    )
    (net (code "91") (name "Net-(LD5A-C)") (class "Default")
      (node (ref "LD5") (pin "1") (pinfunction "C_1") (pintype "passive"))
      (node (ref "R67") (pin "1") (pinfunction "1_1") (pintype "passive"))
    )
    (net (code "92") (name "Net-(LD5B-C)") (class "Default")
      (node (ref "LD5") (pin "3") (pinfunction "C_3") (pintype "passive"))
      (node (ref "R66") (pin "1") (pinfunction "1_1") (pintype "passive"))
    )
    (net (code "93") (name "Net-(T1-D)") (class "Default")
      (node (ref "R58") (pin "2") (pinfunction "2_2") (pintype "passive"))
      (node (ref "T1") (pin "3") (pinfunction "D_3") (pintype "passive"))
    )
    (net (code "94") (name "Net-(T2-D)") (class "Default")
      (node (ref "R59") (pin "2") (pinfunction "2_2") (pintype "passive"))
      (node (ref "T2") (pin "3") (pinfunction "D_3") (pintype "passive"))
    )
    (net (code "95") (name "Net-(T3-D)") (class "Default")
      (node (ref "R60") (pin "2") (pinfunction "2_2") (pintype "passive"))
      (node (ref "T3") (pin "3") (pinfunction "D_3") (pintype "passive"))
    )
    (net (code "96") (name "Net-(T4-D)") (class "Default")
      (node (ref "R61") (pin "2") (pinfunction "2_2") (pintype "passive"))
      (node (ref "T4") (pin "3") (pinfunction "D_3") (pintype "passive"))
    )
    (net (code "97") (name "Net-(T5-D)") (class "Default")
      (node (ref "R62") (pin "2") (pinfunction "2_2") (pintype "passive"))
      (node (ref "T5") (pin "3") (pinfunction "D_3") (pintype "passive"))
    )
    (net (code "98") (name "Net-(T6-D)") (class "Default")
      (node (ref "R63") (pin "2") (pinfunction "2_2") (pintype "passive"))
      (node (ref "T6") (pin "3") (pinfunction "D_3") (pintype "passive"))
    )
    (net (code "99") (name "Net-(T7-D)") (class "Default")
      (node (ref "R64") (pin "2") (pinfunction "2_2") (pintype "passive"))
      (node (ref "T7") (pin "3") (pinfunction "D_3") (pintype "passive"))
    )
    (net (code "100") (name "Net-(T8-D)") (class "Default")
      (node (ref "R65") (pin "2") (pinfunction "2_2") (pintype "passive"))
      (node (ref "T8") (pin "3") (pinfunction "D_3") (pintype "passive"))
    )
    (net (code "101") (name "P3V3") (class "Default")
      (node (ref "C57") (pin "2") (pinfunction "2_2") (pintype "passive"))
      (node (ref "C94") (pin "2") (pinfunction "2_2") (pintype "passive"))
      (node (ref "IC10") (pin "10") (pinfunction "~{SRCLR}_10") (pintype "input"))
      (node (ref "IC10") (pin "16") (pinfunction "VCC_16") (pintype "power_in"))
      (node (ref "IC11") (pin "10") (pinfunction "~{SRCLR}_10") (pintype "input"))
      (node (ref "IC11") (pin "16") (pinfunction "VCC_16") (pintype "power_in"))
      (node (ref "LD1") (pin "2") (pinfunction "A_2") (pintype "passive"))
      (node (ref "LD1") (pin "4") (pinfunction "A_4") (pintype "passive"))
      (node (ref "LD2") (pin "2") (pinfunction "A_2") (pintype "passive"))
      (node (ref "LD2") (pin "4") (pinfunction "A_4") (pintype "passive"))
      (node (ref "LD3") (pin "2") (pinfunction "A_2") (pintype "passive"))
      (node (ref "LD3") (pin "4") (pinfunction "A_4") (pintype "passive"))
      (node (ref "LD4") (pin "2") (pinfunction "A_2") (pintype "passive"))
      (node (ref "LD4") (pin "4") (pinfunction "A_4") (pintype "passive"))
      (node (ref "LD5") (pin "2") (pinfunction "A_2") (pintype "passive"))
      (node (ref "R12") (pin "1") (pinfunction "1_1") (pintype "passive"))
      (node (ref "R13") (pin "1") (pinfunction "1_1") (pintype "passive"))
      (node (ref "R49") (pin "1") (pinfunction "1_1") (pintype "passive"))
      (node (ref "R5") (pin "1") (pinfunction "1_1") (pintype "passive"))
      (node (ref "R68") (pin "1") (pinfunction "1_1") (pintype "passive"))
      (node (ref "R69") (pin "1") (pinfunction "1_1") (pintype "passive"))
      (node (ref "R70") (pin "1") (pinfunction "1_1") (pintype "passive"))
      (node (ref "R71") (pin "1") (pinfunction "1_1") (pintype "passive"))
    )
    (net (code "102") (name "P3V3_MP1") (class "Default")
      (node (ref "LD5") (pin "4") (pinfunction "A_4") (pintype "passive"))
    )
    (net (code "103") (name "P13V0") (class "Default")
      (node (ref "R3") (pin "2") (pinfunction "2_2") (pintype "passive"))
    )
  )
)
